# Driver_Led_final.net
KiCad netlist of a schematic drawn in EAGLE
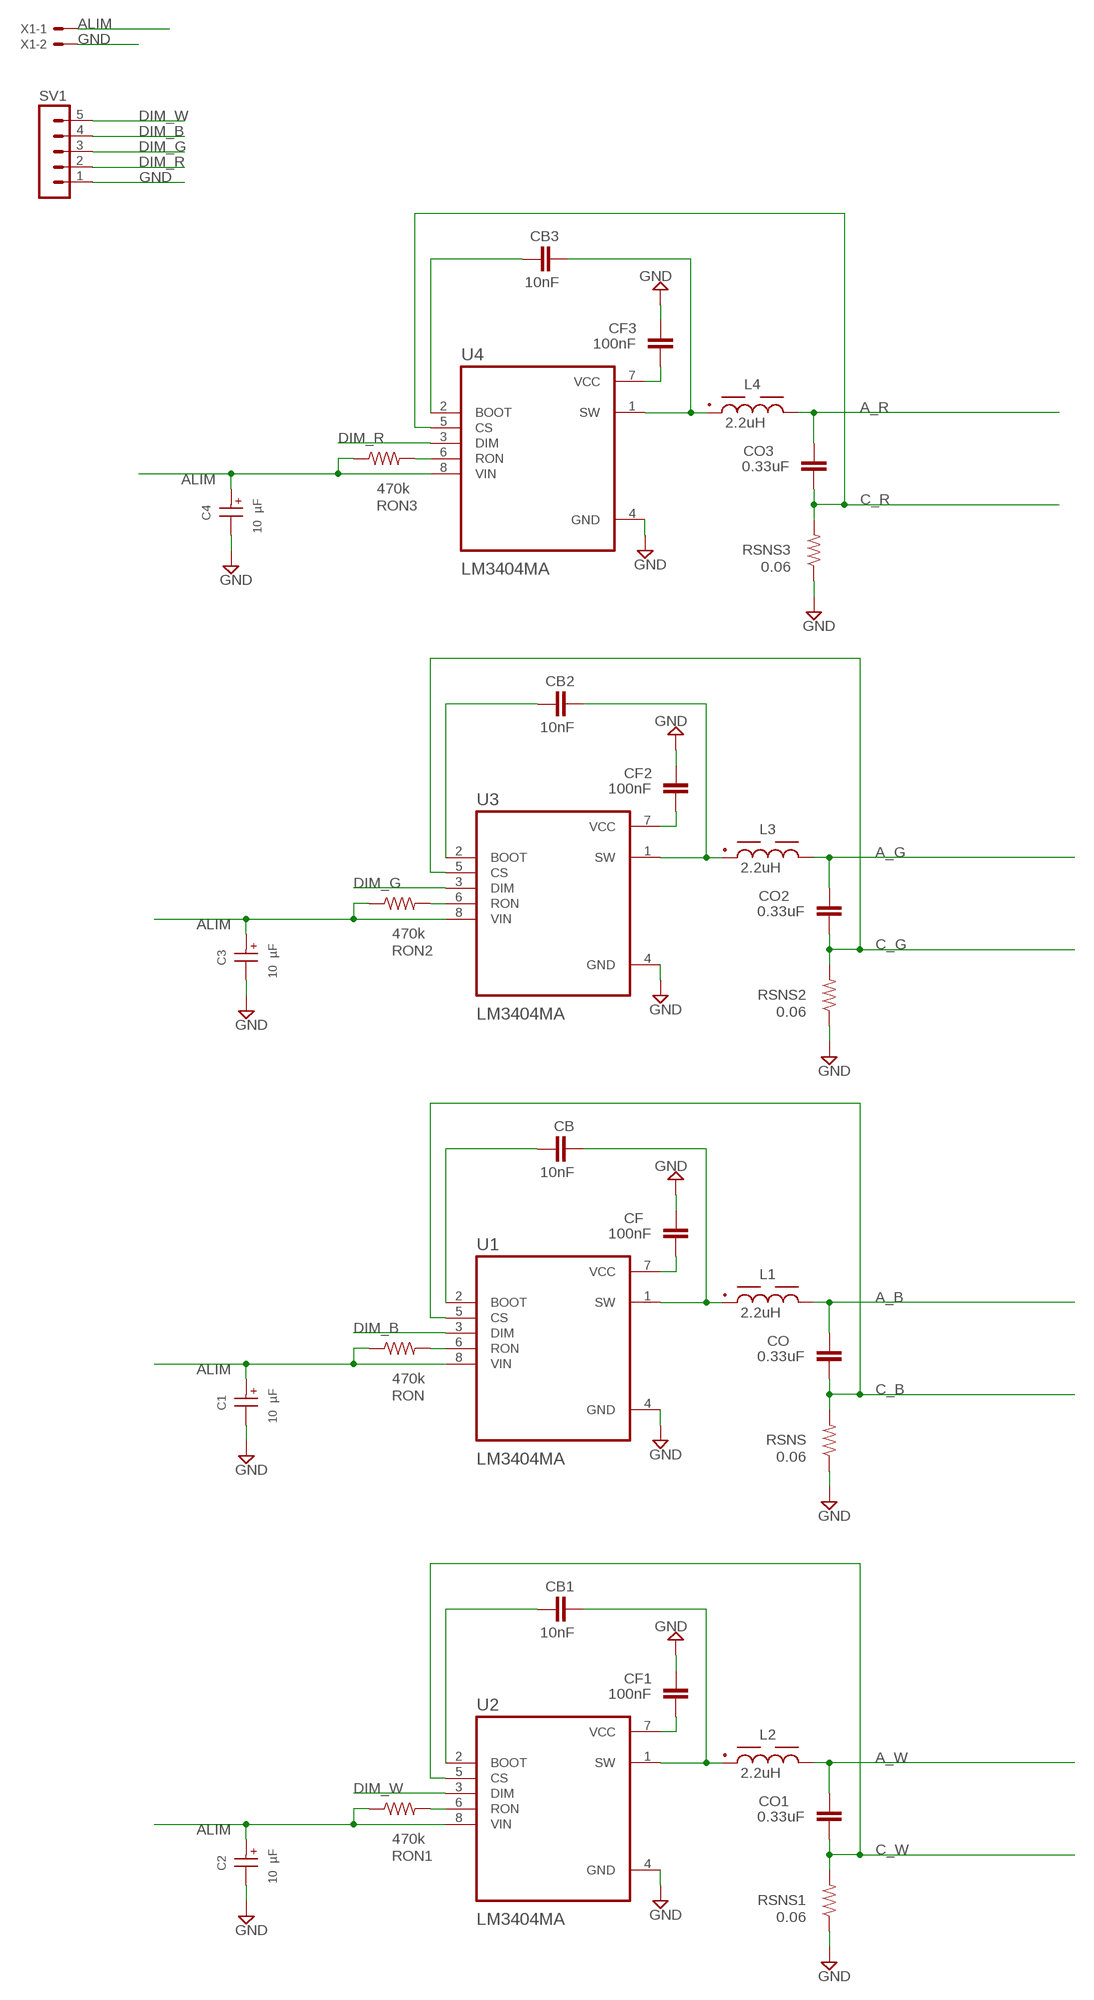
[diagram p0: schematic, sheet 1, part 1 of 2]
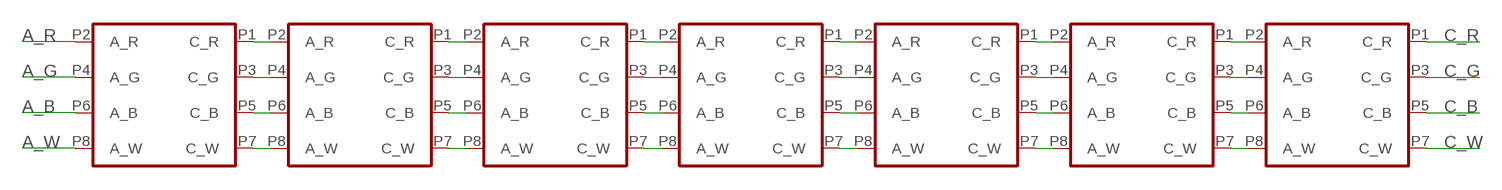
[diagram p1: schematic, sheet 1, part 2 of 2]

(export (version "E")
  (design (tool "Eeschema 10.0.6"))
  (components
    (comp (ref "C1")
      (value "10 µF")
      (footprint "eagle-import:WCAP-ASLL_4X5.5(DXL)")
      (libsource (lib "eagle-import") (part "WCAP-ASLL_4X5.5_865060440001"))
    )
    (comp (ref "C2")
      (value "10 µF")
      (footprint "eagle-import:WCAP-ASLL_4X5.5(DXL)")
      (libsource (lib "eagle-import") (part "WCAP-ASLL_4X5.5_865060440001"))
    )
    (comp (ref "C3")
      (value "10 µF")
      (footprint "eagle-import:WCAP-ASLL_4X5.5(DXL)")
      (libsource (lib "eagle-import") (part "WCAP-ASLL_4X5.5_865060440001"))
    )
    (comp (ref "C4")
      (value "10 µF")
      (footprint "eagle-import:WCAP-ASLL_4X5.5(DXL)")
      (libsource (lib "eagle-import") (part "WCAP-ASLL_4X5.5_865060440001"))
    )
    (comp (ref "CB")
      (value "10nF")
      (footprint "eagle-import:C0603")
      (libsource (lib "eagle-import") (part "C-EUC0603"))
    )
    (comp (ref "CB1")
      (value "10nF")
      (footprint "eagle-import:C0603")
      (libsource (lib "eagle-import") (part "C-EUC0603"))
    )
    (comp (ref "CB2")
      (value "10nF")
      (footprint "eagle-import:C0603")
      (libsource (lib "eagle-import") (part "C-EUC0603"))
    )
    (comp (ref "CB3")
      (value "10nF")
      (footprint "eagle-import:C0603")
      (libsource (lib "eagle-import") (part "C-EUC0603"))
    )
    (comp (ref "CF")
      (value "100nF")
      (footprint "eagle-import:C0603")
      (libsource (lib "eagle-import") (part "C-EUC0603"))
    )
    (comp (ref "CF1")
      (value "100nF")
      (footprint "eagle-import:C0603")
      (libsource (lib "eagle-import") (part "C-EUC0603"))
    )
    (comp (ref "CF2")
      (value "100nF")
      (footprint "eagle-import:C0603")
      (libsource (lib "eagle-import") (part "C-EUC0603"))
    )
    (comp (ref "CF3")
      (value "100nF")
      (footprint "eagle-import:C0603")
      (libsource (lib "eagle-import") (part "C-EUC0603"))
    )
    (comp (ref "CO")
      (value "0.33uF")
      (footprint "eagle-import:C0603")
      (libsource (lib "eagle-import") (part "C-EUC0603"))
    )
    (comp (ref "CO1")
      (value "0.33uF")
      (footprint "eagle-import:C0603")
      (libsource (lib "eagle-import") (part "C-EUC0603"))
    )
    (comp (ref "CO2")
      (value "0.33uF")
      (footprint "eagle-import:C0603")
      (libsource (lib "eagle-import") (part "C-EUC0603"))
    )
    (comp (ref "CO3")
      (value "0.33uF")
      (footprint "eagle-import:C0603")
      (libsource (lib "eagle-import") (part "C-EUC0603"))
    )
    (comp (ref "L1")
      (value "2.2uH")
      (footprint "eagle-import:WE-PDA_1260")
      (libsource (lib "eagle-import") (part "WE-PDA_1260_784771022"))
    )
    (comp (ref "L2")
      (value "2.2uH")
      (footprint "eagle-import:WE-PDA_1260")
      (libsource (lib "eagle-import") (part "WE-PDA_1260_784771022"))
    )
    (comp (ref "L3")
      (value "2.2uH")
      (footprint "eagle-import:WE-PDA_1260")
      (libsource (lib "eagle-import") (part "WE-PDA_1260_784771022"))
    )
    (comp (ref "L4")
      (value "2.2uH")
      (footprint "eagle-import:WE-PDA_1260")
      (libsource (lib "eagle-import") (part "WE-PDA_1260_784771022"))
    )
    (comp (ref "RON")
      (value "470k")
      (footprint "eagle-import:R0603")
      (libsource (lib "eagle-import") (part "R-US_R0603"))
    )
    (comp (ref "RON1")
      (value "470k")
      (footprint "eagle-import:R0603")
      (libsource (lib "eagle-import") (part "R-US_R0603"))
    )
    (comp (ref "RON2")
      (value "470k")
      (footprint "eagle-import:R0603")
      (libsource (lib "eagle-import") (part "R-US_R0603"))
    )
    (comp (ref "RON3")
      (value "470k")
      (footprint "eagle-import:R0603")
      (libsource (lib "eagle-import") (part "R-US_R0603"))
    )
    (comp (ref "RSNS")
      (value "0.06")
      (footprint "eagle-import:R0603")
      (libsource (lib "eagle-import") (part "R-US_R0603"))
    )
    (comp (ref "RSNS1")
      (value "0.06")
      (footprint "eagle-import:R0603")
      (libsource (lib "eagle-import") (part "R-US_R0603"))
    )
    (comp (ref "RSNS2")
      (value "0.06")
      (footprint "eagle-import:R0603")
      (libsource (lib "eagle-import") (part "R-US_R0603"))
    )
    (comp (ref "RSNS3")
      (value "0.06")
      (footprint "eagle-import:R0603")
      (libsource (lib "eagle-import") (part "R-US_R0603"))
    )
    (comp (ref "SV1")
      (value "MA05-1")
      (footprint "eagle-import:MA05-1")
      (libsource (lib "eagle-import") (part "MA05-1"))
    )
    (comp (ref "U$1")
      (value "LE_RTDUW_S2WM_DEVICE")
      (footprint "eagle-import:LE_RTDUW_S2WM_FOOTPRINT")
      (libsource (lib "eagle-import") (part "LE_RTDUW_S2WM_DEVICE"))
    )
    (comp (ref "U$2")
      (value "LE_RTDUW_S2WM_DEVICE")
      (footprint "eagle-import:LE_RTDUW_S2WM_FOOTPRINT")
      (libsource (lib "eagle-import") (part "LE_RTDUW_S2WM_DEVICE"))
    )
    (comp (ref "U$3")
      (value "LE_RTDUW_S2WM_DEVICE")
      (footprint "eagle-import:LE_RTDUW_S2WM_FOOTPRINT")
      (libsource (lib "eagle-import") (part "LE_RTDUW_S2WM_DEVICE"))
    )
    (comp (ref "U$4")
      (value "LE_RTDUW_S2WM_DEVICE")
      (footprint "eagle-import:LE_RTDUW_S2WM_FOOTPRINT")
      (libsource (lib "eagle-import") (part "LE_RTDUW_S2WM_DEVICE"))
    )
    (comp (ref "U$5")
      (value "LE_RTDUW_S2WM_DEVICE")
      (footprint "eagle-import:LE_RTDUW_S2WM_FOOTPRINT")
      (libsource (lib "eagle-import") (part "LE_RTDUW_S2WM_DEVICE"))
    )
    (comp (ref "U$6")
      (value "LE_RTDUW_S2WM_DEVICE")
      (footprint "eagle-import:LE_RTDUW_S2WM_FOOTPRINT")
      (libsource (lib "eagle-import") (part "LE_RTDUW_S2WM_DEVICE"))
    )
    (comp (ref "U$7")
      (value "LE_RTDUW_S2WM_DEVICE")
      (footprint "eagle-import:LE_RTDUW_S2WM_FOOTPRINT")
      (libsource (lib "eagle-import") (part "LE_RTDUW_S2WM_DEVICE"))
    )
    (comp (ref "U1")
      (value "LM3404MA")
      (footprint "eagle-import:SOIC127P599X175-8N")
      (fields (field (name "MF") "Texas Instruments") (field (name "MP") "LM3404MA/NOPB"))
      (libsource (lib "eagle-import") (part "LM3404MA"))
    )
    (comp (ref "U2")
      (value "LM3404MA")
      (footprint "eagle-import:SOIC127P599X175-8N")
      (fields (field (name "MF") "Texas Instruments") (field (name "MP") "LM3404MA/NOPB"))
      (libsource (lib "eagle-import") (part "LM3404MA"))
    )
    (comp (ref "U3")
      (value "LM3404MA")
      (footprint "eagle-import:SOIC127P599X175-8N")
      (fields (field (name "MF") "Texas Instruments") (field (name "MP") "LM3404MA/NOPB"))
      (libsource (lib "eagle-import") (part "LM3404MA"))
    )
    (comp (ref "U4")
      (value "LM3404MA")
      (footprint "eagle-import:SOIC127P599X175-8N")
      (fields (field (name "MF") "Texas Instruments") (field (name "MP") "LM3404MA/NOPB"))
      (libsource (lib "eagle-import") (part "LM3404MA"))
    )
    (comp (ref "X1")
      (value "22-23-2021")
      (footprint "eagle-import:22-23-2021")
      (fields (field (name "MF") "MOLEX"))
      (libsource (lib "eagle-import") (part "22-23-2021"))
    )
  )
  (nets
    (net (code "1") (name "/ALIM") (class "Default")
      (node (ref "C1") (pin "1") (pinfunction "+_1") (pintype "passive"))
      (node (ref "C2") (pin "1") (pinfunction "+_1") (pintype "passive"))
      (node (ref "C3") (pin "1") (pinfunction "+_1") (pintype "passive"))
      (node (ref "C4") (pin "1") (pinfunction "+_1") (pintype "passive"))
      (node (ref "RON") (pin "1") (pinfunction "1_1") (pintype "passive"))
      (node (ref "RON1") (pin "1") (pinfunction "1_1") (pintype "passive"))
      (node (ref "RON2") (pin "1") (pinfunction "1_1") (pintype "passive"))
      (node (ref "RON3") (pin "1") (pinfunction "1_1") (pintype "passive"))
      (node (ref "U1") (pin "8") (pinfunction "VIN_8") (pintype "input"))
      (node (ref "U2") (pin "8") (pinfunction "VIN_8") (pintype "input"))
      (node (ref "U3") (pin "8") (pinfunction "VIN_8") (pintype "input"))
      (node (ref "U4") (pin "8") (pinfunction "VIN_8") (pintype "input"))
      (node (ref "X1") (pin "1") (pinfunction "S_1") (pintype "passive"))
    )
    (net (code "2") (name "/A_B") (class "Default")
      (node (ref "CO") (pin "2") (pinfunction "2_2") (pintype "passive"))
      (node (ref "L1") (pin "2") (pinfunction "2_2") (pintype "passive"))
      (node (ref "U$1") (pin "P6") (pinfunction "A_B_P6") (pintype "bidirectional"))
    )
    (net (code "3") (name "/A_G") (class "Default")
      (node (ref "CO2") (pin "2") (pinfunction "2_2") (pintype "passive"))
      (node (ref "L3") (pin "2") (pinfunction "2_2") (pintype "passive"))
      (node (ref "U$1") (pin "P4") (pinfunction "A_G_P4") (pintype "power_in"))
    )
    (net (code "4") (name "/A_R") (class "Default")
      (node (ref "CO3") (pin "2") (pinfunction "2_2") (pintype "passive"))
      (node (ref "L4") (pin "2") (pinfunction "2_2") (pintype "passive"))
      (node (ref "U$1") (pin "P2") (pinfunction "A_R_P2") (pintype "power_in"))
    )
    (net (code "5") (name "/A_W") (class "Default")
      (node (ref "CO1") (pin "2") (pinfunction "2_2") (pintype "passive"))
      (node (ref "L2") (pin "2") (pinfunction "2_2") (pintype "passive"))
      (node (ref "U$1") (pin "P8") (pinfunction "A_W_P8") (pintype "bidirectional"))
    )
    (net (code "6") (name "/C_B") (class "Default")
      (node (ref "CO") (pin "1") (pinfunction "1_1") (pintype "passive"))
      (node (ref "RSNS") (pin "2") (pinfunction "2_2") (pintype "passive"))
      (node (ref "U$7") (pin "P5") (pinfunction "C_B_P5") (pintype "bidirectional"))
      (node (ref "U1") (pin "5") (pinfunction "CS_5") (pintype "input"))
    )
    (net (code "7") (name "/C_G") (class "Default")
      (node (ref "CO2") (pin "1") (pinfunction "1_1") (pintype "passive"))
      (node (ref "RSNS2") (pin "2") (pinfunction "2_2") (pintype "passive"))
      (node (ref "U$7") (pin "P3") (pinfunction "C_G_P3") (pintype "bidirectional"))
      (node (ref "U3") (pin "5") (pinfunction "CS_5") (pintype "input"))
    )
    (net (code "8") (name "/C_R") (class "Default")
      (node (ref "CO3") (pin "1") (pinfunction "1_1") (pintype "passive"))
      (node (ref "RSNS3") (pin "2") (pinfunction "2_2") (pintype "passive"))
      (node (ref "U$7") (pin "P1") (pinfunction "C_R_P1") (pintype "input"))
      (node (ref "U4") (pin "5") (pinfunction "CS_5") (pintype "input"))
    )
    (net (code "9") (name "/C_W") (class "Default")
      (node (ref "CO1") (pin "1") (pinfunction "1_1") (pintype "passive"))
      (node (ref "RSNS1") (pin "2") (pinfunction "2_2") (pintype "passive"))
      (node (ref "U$7") (pin "P7") (pinfunction "C_W_P7") (pintype "bidirectional"))
      (node (ref "U2") (pin "5") (pinfunction "CS_5") (pintype "input"))
    )
    (net (code "10") (name "/DIM_B") (class "Default")
      (node (ref "SV1") (pin "4") (pinfunction "4_4") (pintype "passive"))
      (node (ref "U1") (pin "3") (pinfunction "DIM_3") (pintype "input"))
    )
    (net (code "11") (name "/DIM_G") (class "Default")
      (node (ref "SV1") (pin "3") (pinfunction "3_3") (pintype "passive"))
      (node (ref "U3") (pin "3") (pinfunction "DIM_3") (pintype "input"))
    )
    (net (code "12") (name "/DIM_R") (class "Default")
      (node (ref "SV1") (pin "2") (pinfunction "2_2") (pintype "passive"))
      (node (ref "U4") (pin "3") (pinfunction "DIM_3") (pintype "input"))
    )
    (net (code "13") (name "/DIM_W") (class "Default")
      (node (ref "SV1") (pin "5") (pinfunction "5_5") (pintype "passive"))
      (node (ref "U2") (pin "3") (pinfunction "DIM_3") (pintype "input"))
    )
    (net (code "14") (name "GND") (class "Default")
      (node (ref "C1") (pin "2") (pinfunction "-_2") (pintype "passive"))
      (node (ref "C2") (pin "2") (pinfunction "-_2") (pintype "passive"))
      (node (ref "C3") (pin "2") (pinfunction "-_2") (pintype "passive"))
      (node (ref "C4") (pin "2") (pinfunction "-_2") (pintype "passive"))
      (node (ref "CF") (pin "1") (pinfunction "1_1") (pintype "passive"))
      (node (ref "CF1") (pin "1") (pinfunction "1_1") (pintype "passive"))
      (node (ref "CF2") (pin "1") (pinfunction "1_1") (pintype "passive"))
      (node (ref "CF3") (pin "1") (pinfunction "1_1") (pintype "passive"))
      (node (ref "RSNS") (pin "1") (pinfunction "1_1") (pintype "passive"))
      (node (ref "RSNS1") (pin "1") (pinfunction "1_1") (pintype "passive"))
      (node (ref "RSNS2") (pin "1") (pinfunction "1_1") (pintype "passive"))
      (node (ref "RSNS3") (pin "1") (pinfunction "1_1") (pintype "passive"))
      (node (ref "SV1") (pin "1") (pinfunction "1_1") (pintype "passive"))
      (node (ref "U1") (pin "4") (pinfunction "GND_4") (pintype "power_in"))
      (node (ref "U2") (pin "4") (pinfunction "GND_4") (pintype "power_in"))
      (node (ref "U3") (pin "4") (pinfunction "GND_4") (pintype "power_in"))
      (node (ref "U4") (pin "4") (pinfunction "GND_4") (pintype "power_in"))
      (node (ref "X1") (pin "2") (pinfunction "S_2") (pintype "passive"))
    )
    (net (code "15") (name "Net-(U$1-C_B)") (class "Default")
      (node (ref "U$1") (pin "P5") (pinfunction "C_B_P5") (pintype "bidirectional"))
      (node (ref "U$2") (pin "P6") (pinfunction "A_B_P6") (pintype "bidirectional"))
    )
    (net (code "16") (name "Net-(U$1-C_G)") (class "Default")
      (node (ref "U$1") (pin "P3") (pinfunction "C_G_P3") (pintype "bidirectional"))
      (node (ref "U$2") (pin "P4") (pinfunction "A_G_P4") (pintype "power_in"))
    )
    (net (code "17") (name "Net-(U$1-C_R)") (class "Default")
      (node (ref "U$1") (pin "P1") (pinfunction "C_R_P1") (pintype "input"))
      (node (ref "U$2") (pin "P2") (pinfunction "A_R_P2") (pintype "power_in"))
    )
    (net (code "18") (name "Net-(U$1-C_W)") (class "Default")
      (node (ref "U$1") (pin "P7") (pinfunction "C_W_P7") (pintype "bidirectional"))
      (node (ref "U$2") (pin "P8") (pinfunction "A_W_P8") (pintype "bidirectional"))
    )
    (net (code "19") (name "Net-(U$2-C_B)") (class "Default")
      (node (ref "U$2") (pin "P5") (pinfunction "C_B_P5") (pintype "bidirectional"))
      (node (ref "U$3") (pin "P6") (pinfunction "A_B_P6") (pintype "bidirectional"))
    )
    (net (code "20") (name "Net-(U$2-C_G)") (class "Default")
      (node (ref "U$2") (pin "P3") (pinfunction "C_G_P3") (pintype "bidirectional"))
      (node (ref "U$3") (pin "P4") (pinfunction "A_G_P4") (pintype "power_in"))
    )
    (net (code "21") (name "Net-(U$2-C_R)") (class "Default")
      (node (ref "U$2") (pin "P1") (pinfunction "C_R_P1") (pintype "input"))
      (node (ref "U$3") (pin "P2") (pinfunction "A_R_P2") (pintype "power_in"))
    )
    (net (code "22") (name "Net-(U$2-C_W)") (class "Default")
      (node (ref "U$2") (pin "P7") (pinfunction "C_W_P7") (pintype "bidirectional"))
      (node (ref "U$3") (pin "P8") (pinfunction "A_W_P8") (pintype "bidirectional"))
    )
    (net (code "23") (name "Net-(U$3-C_B)") (class "Default")
      (node (ref "U$3") (pin "P5") (pinfunction "C_B_P5") (pintype "bidirectional"))
      (node (ref "U$4") (pin "P6") (pinfunction "A_B_P6") (pintype "bidirectional"))
    )
    (net (code "24") (name "Net-(U$3-C_G)") (class "Default")
      (node (ref "U$3") (pin "P3") (pinfunction "C_G_P3") (pintype "bidirectional"))
      (node (ref "U$4") (pin "P4") (pinfunction "A_G_P4") (pintype "power_in"))
    )
    (net (code "25") (name "Net-(U$3-C_R)") (class "Default")
      (node (ref "U$3") (pin "P1") (pinfunction "C_R_P1") (pintype "input"))
      (node (ref "U$4") (pin "P2") (pinfunction "A_R_P2") (pintype "power_in"))
    )
    (net (code "26") (name "Net-(U$3-C_W)") (class "Default")
      (node (ref "U$3") (pin "P7") (pinfunction "C_W_P7") (pintype "bidirectional"))
      (node (ref "U$4") (pin "P8") (pinfunction "A_W_P8") (pintype "bidirectional"))
    )
    (net (code "27") (name "Net-(U$4-C_B)") (class "Default")
      (node (ref "U$4") (pin "P5") (pinfunction "C_B_P5") (pintype "bidirectional"))
      (node (ref "U$5") (pin "P6") (pinfunction "A_B_P6") (pintype "bidirectional"))
    )
    (net (code "28") (name "Net-(U$4-C_G)") (class "Default")
      (node (ref "U$4") (pin "P3") (pinfunction "C_G_P3") (pintype "bidirectional"))
      (node (ref "U$5") (pin "P4") (pinfunction "A_G_P4") (pintype "power_in"))
    )
    (net (code "29") (name "Net-(U$4-C_R)") (class "Default")
      (node (ref "U$4") (pin "P1") (pinfunction "C_R_P1") (pintype "input"))
      (node (ref "U$5") (pin "P2") (pinfunction "A_R_P2") (pintype "power_in"))
    )
    (net (code "30") (name "Net-(U$4-C_W)") (class "Default")
      (node (ref "U$4") (pin "P7") (pinfunction "C_W_P7") (pintype "bidirectional"))
      (node (ref "U$5") (pin "P8") (pinfunction "A_W_P8") (pintype "bidirectional"))
    )
    (net (code "31") (name "Net-(U$5-C_B)") (class "Default")
      (node (ref "U$5") (pin "P5") (pinfunction "C_B_P5") (pintype "bidirectional"))
      (node (ref "U$6") (pin "P6") (pinfunction "A_B_P6") (pintype "bidirectional"))
    )
    (net (code "32") (name "Net-(U$5-C_G)") (class "Default")
      (node (ref "U$5") (pin "P3") (pinfunction "C_G_P3") (pintype "bidirectional"))
      (node (ref "U$6") (pin "P4") (pinfunction "A_G_P4") (pintype "power_in"))
    )
    (net (code "33") (name "Net-(U$5-C_R)") (class "Default")
      (node (ref "U$5") (pin "P1") (pinfunction "C_R_P1") (pintype "input"))
      (node (ref "U$6") (pin "P2") (pinfunction "A_R_P2") (pintype "power_in"))
    )
    (net (code "34") (name "Net-(U$5-C_W)") (class "Default")
      (node (ref "U$5") (pin "P7") (pinfunction "C_W_P7") (pintype "bidirectional"))
      (node (ref "U$6") (pin "P8") (pinfunction "A_W_P8") (pintype "bidirectional"))
    )
    (net (code "35") (name "Net-(U$6-C_B)") (class "Default")
      (node (ref "U$6") (pin "P5") (pinfunction "C_B_P5") (pintype "bidirectional"))
      (node (ref "U$7") (pin "P6") (pinfunction "A_B_P6") (pintype "bidirectional"))
    )
    (net (code "36") (name "Net-(U$6-C_G)") (class "Default")
      (node (ref "U$6") (pin "P3") (pinfunction "C_G_P3") (pintype "bidirectional"))
      (node (ref "U$7") (pin "P4") (pinfunction "A_G_P4") (pintype "power_in"))
    )
    (net (code "37") (name "Net-(U$6-C_R)") (class "Default")
      (node (ref "U$6") (pin "P1") (pinfunction "C_R_P1") (pintype "input"))
      (node (ref "U$7") (pin "P2") (pinfunction "A_R_P2") (pintype "power_in"))
    )
    (net (code "38") (name "Net-(U$6-C_W)") (class "Default")
      (node (ref "U$6") (pin "P7") (pinfunction "C_W_P7") (pintype "bidirectional"))
      (node (ref "U$7") (pin "P8") (pinfunction "A_W_P8") (pintype "bidirectional"))
    )
    (net (code "39") (name "Net-(U1-BOOT)") (class "Default")
      (node (ref "CB") (pin "1") (pinfunction "1_1") (pintype "passive"))
      (node (ref "U1") (pin "2") (pinfunction "BOOT_2") (pintype "input"))
    )
    (net (code "40") (name "Net-(U1-RON)") (class "Default")
      (node (ref "RON") (pin "2") (pinfunction "2_2") (pintype "passive"))
      (node (ref "U1") (pin "6") (pinfunction "RON_6") (pintype "input"))
    )
    (net (code "41") (name "Net-(U1-SW)") (class "Default")
      (node (ref "CB") (pin "2") (pinfunction "2_2") (pintype "passive"))
      (node (ref "L1") (pin "1") (pinfunction "1_1") (pintype "passive"))
      (node (ref "U1") (pin "1") (pinfunction "SW_1") (pintype "output"))
    )
    (net (code "42") (name "Net-(U1-VCC)") (class "Default")
      (node (ref "CF") (pin "2") (pinfunction "2_2") (pintype "passive"))
      (node (ref "U1") (pin "7") (pinfunction "VCC_7") (pintype "power_in"))
    )
    (net (code "43") (name "Net-(U2-BOOT)") (class "Default")
      (node (ref "CB1") (pin "1") (pinfunction "1_1") (pintype "passive"))
      (node (ref "U2") (pin "2") (pinfunction "BOOT_2") (pintype "input"))
    )
    (net (code "44") (name "Net-(U2-RON)") (class "Default")
      (node (ref "RON1") (pin "2") (pinfunction "2_2") (pintype "passive"))
      (node (ref "U2") (pin "6") (pinfunction "RON_6") (pintype "input"))
    )
    (net (code "45") (name "Net-(U2-SW)") (class "Default")
      (node (ref "CB1") (pin "2") (pinfunction "2_2") (pintype "passive"))
      (node (ref "L2") (pin "1") (pinfunction "1_1") (pintype "passive"))
      (node (ref "U2") (pin "1") (pinfunction "SW_1") (pintype "output"))
    )
    (net (code "46") (name "Net-(U2-VCC)") (class "Default")
      (node (ref "CF1") (pin "2") (pinfunction "2_2") (pintype "passive"))
      (node (ref "U2") (pin "7") (pinfunction "VCC_7") (pintype "power_in"))
    )
    (net (code "47") (name "Net-(U3-BOOT)") (class "Default")
      (node (ref "CB2") (pin "1") (pinfunction "1_1") (pintype "passive"))
      (node (ref "U3") (pin "2") (pinfunction "BOOT_2") (pintype "input"))
    )
    (net (code "48") (name "Net-(U3-RON)") (class "Default")
      (node (ref "RON2") (pin "2") (pinfunction "2_2") (pintype "passive"))
      (node (ref "U3") (pin "6") (pinfunction "RON_6") (pintype "input"))
    )
    (net (code "49") (name "Net-(U3-SW)") (class "Default")
      (node (ref "CB2") (pin "2") (pinfunction "2_2") (pintype "passive"))
      (node (ref "L3") (pin "1") (pinfunction "1_1") (pintype "passive"))
      (node (ref "U3") (pin "1") (pinfunction "SW_1") (pintype "output"))
    )
    (net (code "50") (name "Net-(U3-VCC)") (class "Default")
      (node (ref "CF2") (pin "2") (pinfunction "2_2") (pintype "passive"))
      (node (ref "U3") (pin "7") (pinfunction "VCC_7") (pintype "power_in"))
    )
    (net (code "51") (name "Net-(U4-BOOT)") (class "Default")
      (node (ref "CB3") (pin "1") (pinfunction "1_1") (pintype "passive"))
      (node (ref "U4") (pin "2") (pinfunction "BOOT_2") (pintype "input"))
    )
    (net (code "52") (name "Net-(U4-RON)") (class "Default")
      (node (ref "RON3") (pin "2") (pinfunction "2_2") (pintype "passive"))
      (node (ref "U4") (pin "6") (pinfunction "RON_6") (pintype "input"))
    )
    (net (code "53") (name "Net-(U4-SW)") (class "Default")
      (node (ref "CB3") (pin "2") (pinfunction "2_2") (pintype "passive"))
      (node (ref "L4") (pin "1") (pinfunction "1_1") (pintype "passive"))
      (node (ref "U4") (pin "1") (pinfunction "SW_1") (pintype "output"))
    )
    (net (code "54") (name "Net-(U4-VCC)") (class "Default")
      (node (ref "CF3") (pin "2") (pinfunction "2_2") (pintype "passive"))
      (node (ref "U4") (pin "7") (pinfunction "VCC_7") (pintype "power_in"))
    )
  )
)
